# design.net
KiCad netlist of a schematic drawn in Altium Designer
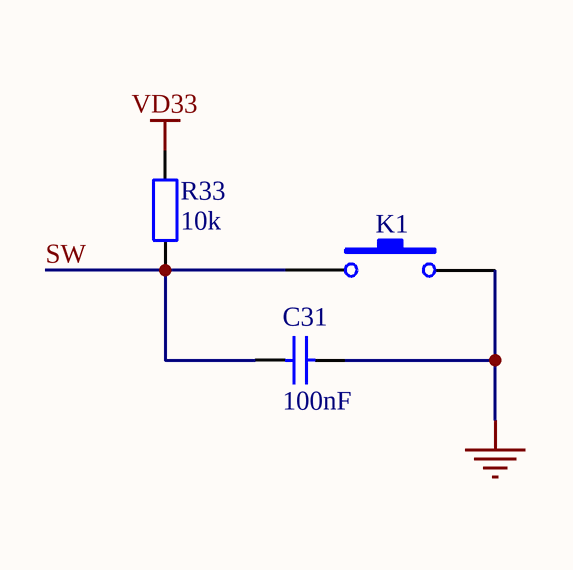
[diagram p0: 暂停.SchDoc]

(export (version "E")
  (design (tool "Eeschema 10.0.6"))
  (components
    (comp (ref "C31")
      (value "100nF")
      (footprint "LC-0805_C")
      (description "100nF��0805��50V,+/-10%")
      (libsource (lib "ECG") (part "Cap"))
    )
    (comp (ref "K1")
      (value "�ᴥ����")
      (footprint "SW6X6")
      (description "�ᴥ����6��6mm,�Ľǲ��")
      (fields (field (name "PUBLISHER") "Altium Limited"))
      (libsource (lib "ECG") (part "SW-PB"))
    )
    (comp (ref "R33")
      (value "10k")
      (footprint "LC-0805_R")
      (description "10k��,0805,��5%")
      (libsource (lib "ECG") (part "R"))
    )
  )
  (nets
    (net (code "1") (name "/SW") (class "Default")
      (node (ref "C31") (pin "1") (pinfunction "1_1") (pintype "passive"))
      (node (ref "K1") (pin "1") (pinfunction "1_1") (pintype "passive"))
      (node (ref "R33") (pin "1") (pintype "passive"))
    )
    (net (code "2") (name "<NO NET>") (class "Default")
      (node (ref "C31") (pin "2") (pinfunction "2_2") (pintype "passive"))
      (node (ref "K1") (pin "2") (pinfunction "2_2") (pintype "passive"))
    )
    (net (code "3") (name "VD33") (class "Default") (node (ref "R33") (pin "2") (pintype "passive")))
  )
)
